# rightboard.net
KiCad netlist of a schematic drawn in EAGLE
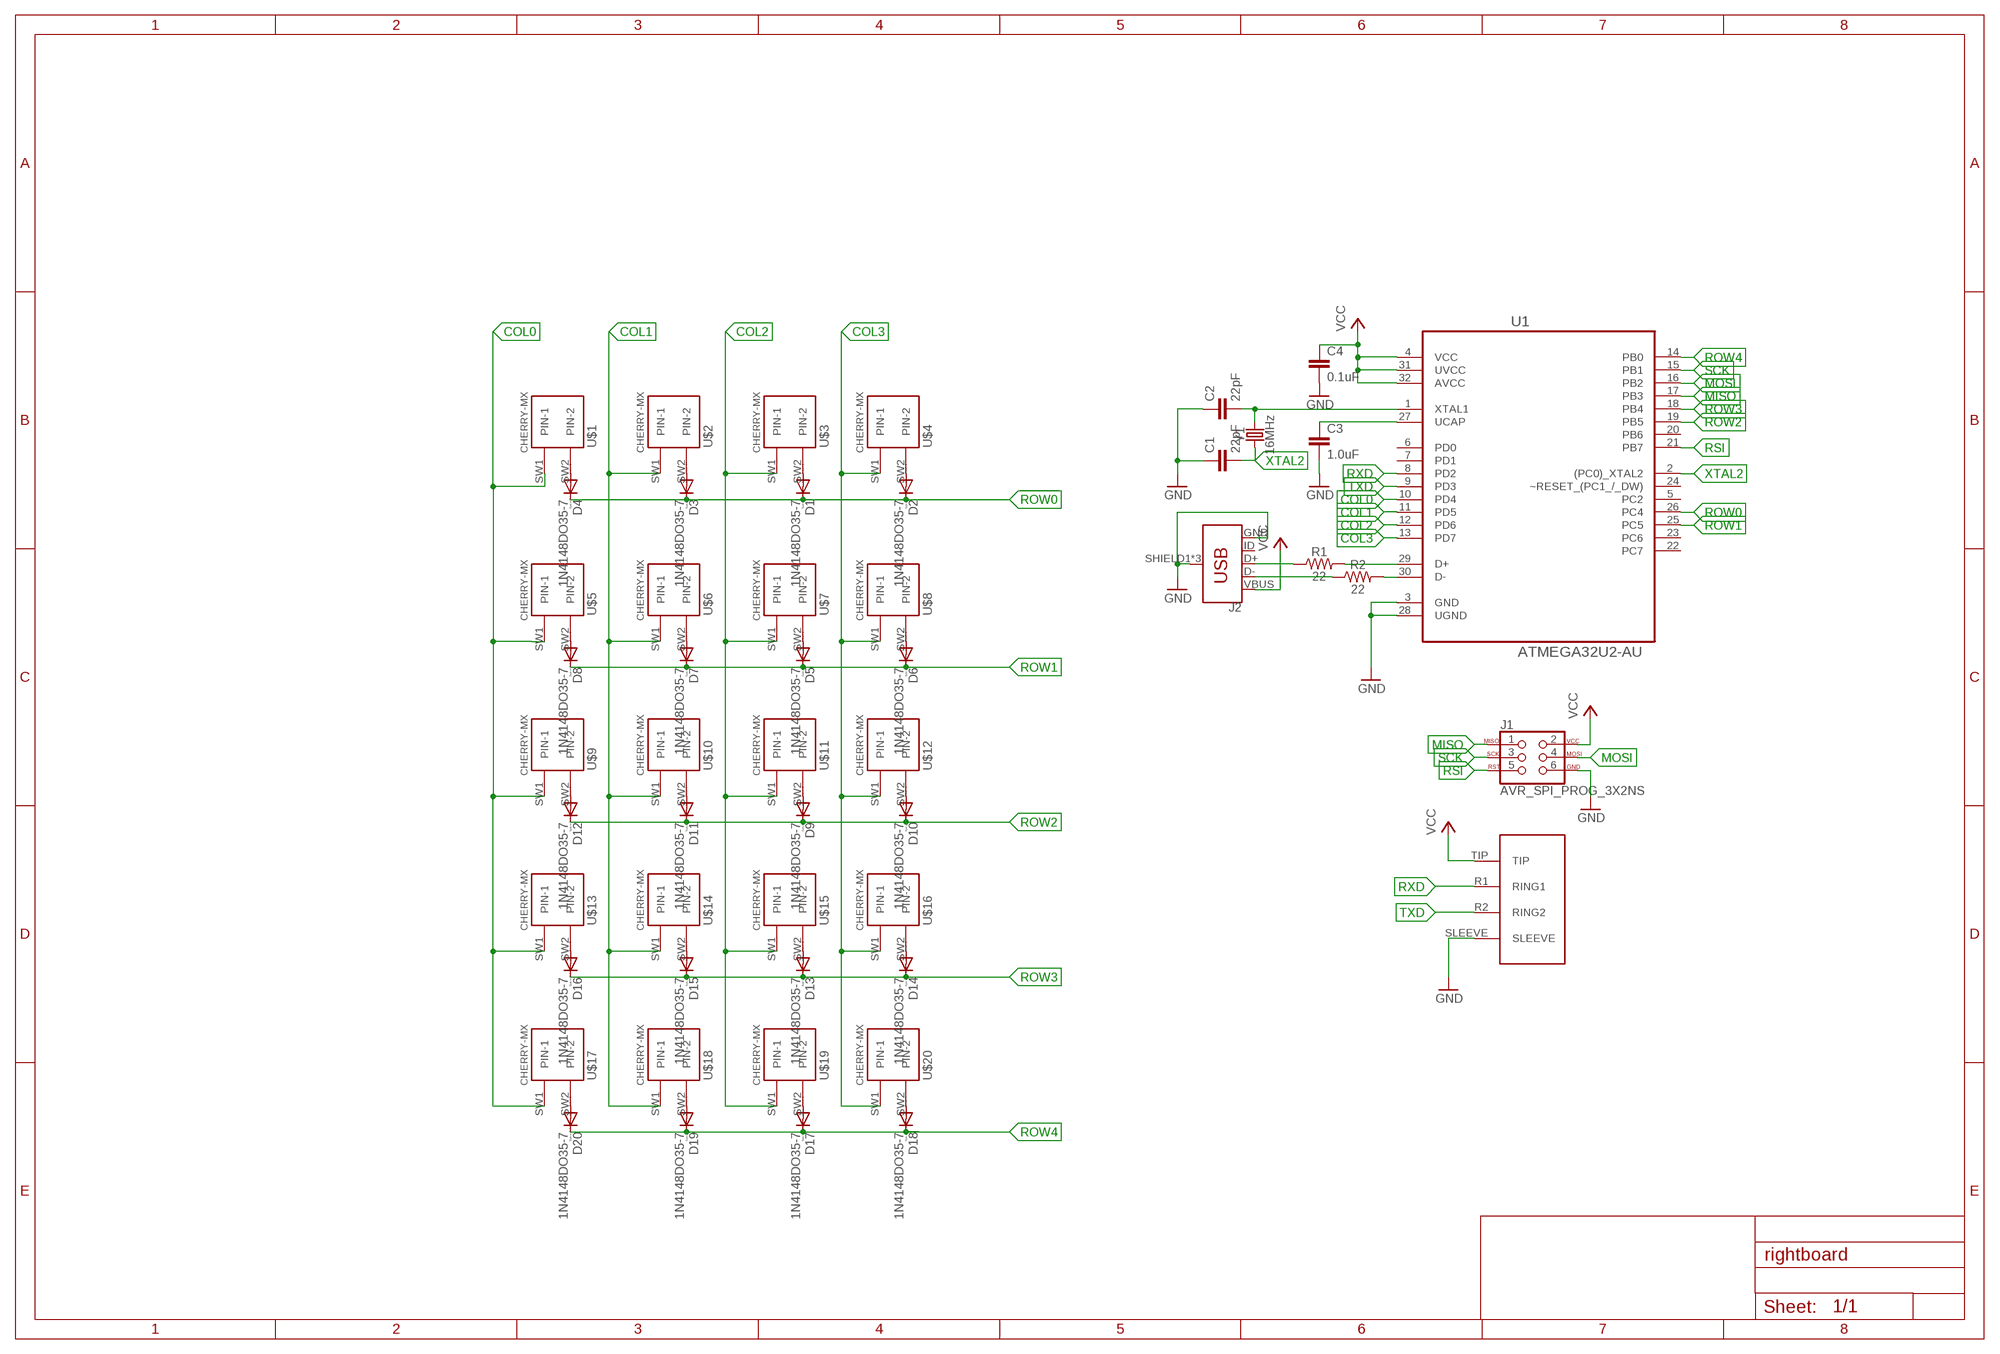
[diagram p0: schematic, sheet 1]

(export (version "E")
  (design (tool "Eeschema 10.0.6"))
  (components
    (comp (ref "C1")
      (value "22pF")
      (footprint "eagle-import:0603")
      (libsource (lib "eagle-import") (part "22PF-0603-50V-5%"))
    )
    (comp (ref "C2")
      (value "22pF")
      (footprint "eagle-import:0603")
      (libsource (lib "eagle-import") (part "22PF-0603-50V-5%"))
    )
    (comp (ref "C3")
      (value "1.0uF")
      (footprint "eagle-import:0603")
      (libsource (lib "eagle-import") (part "1.0UF-0603-16V-10%"))
    )
    (comp (ref "C4")
      (value "0.1uF")
      (footprint "eagle-import:0603")
      (libsource (lib "eagle-import") (part "0.1UF-0603-25V-(+80/-20%)"))
    )
    (comp (ref "D1")
      (value "1N4148DO35-7")
      (footprint "eagle-import:DO35-7")
      (libsource (lib "eagle-import") (part "1N4148DO35-7"))
    )
    (comp (ref "D2")
      (value "1N4148DO35-7")
      (footprint "eagle-import:DO35-7")
      (libsource (lib "eagle-import") (part "1N4148DO35-7"))
    )
    (comp (ref "D3")
      (value "1N4148DO35-7")
      (footprint "eagle-import:DO35-7")
      (libsource (lib "eagle-import") (part "1N4148DO35-7"))
    )
    (comp (ref "D4")
      (value "1N4148DO35-7")
      (footprint "eagle-import:DO35-7")
      (libsource (lib "eagle-import") (part "1N4148DO35-7"))
    )
    (comp (ref "D5")
      (value "1N4148DO35-7")
      (footprint "eagle-import:DO35-7")
      (libsource (lib "eagle-import") (part "1N4148DO35-7"))
    )
    (comp (ref "D6")
      (value "1N4148DO35-7")
      (footprint "eagle-import:DO35-7")
      (libsource (lib "eagle-import") (part "1N4148DO35-7"))
    )
    (comp (ref "D7")
      (value "1N4148DO35-7")
      (footprint "eagle-import:DO35-7")
      (libsource (lib "eagle-import") (part "1N4148DO35-7"))
    )
    (comp (ref "D8")
      (value "1N4148DO35-7")
      (footprint "eagle-import:DO35-7")
      (libsource (lib "eagle-import") (part "1N4148DO35-7"))
    )
    (comp (ref "D9")
      (value "1N4148DO35-7")
      (footprint "eagle-import:DO35-7")
      (libsource (lib "eagle-import") (part "1N4148DO35-7"))
    )
    (comp (ref "D10")
      (value "1N4148DO35-7")
      (footprint "eagle-import:DO35-7")
      (libsource (lib "eagle-import") (part "1N4148DO35-7"))
    )
    (comp (ref "D11")
      (value "1N4148DO35-7")
      (footprint "eagle-import:DO35-7")
      (libsource (lib "eagle-import") (part "1N4148DO35-7"))
    )
    (comp (ref "D12")
      (value "1N4148DO35-7")
      (footprint "eagle-import:DO35-7")
      (libsource (lib "eagle-import") (part "1N4148DO35-7"))
    )
    (comp (ref "D13")
      (value "1N4148DO35-7")
      (footprint "eagle-import:DO35-7")
      (libsource (lib "eagle-import") (part "1N4148DO35-7"))
    )
    (comp (ref "D14")
      (value "1N4148DO35-7")
      (footprint "eagle-import:DO35-7")
      (libsource (lib "eagle-import") (part "1N4148DO35-7"))
    )
    (comp (ref "D15")
      (value "1N4148DO35-7")
      (footprint "eagle-import:DO35-7")
      (libsource (lib "eagle-import") (part "1N4148DO35-7"))
    )
    (comp (ref "D16")
      (value "1N4148DO35-7")
      (footprint "eagle-import:DO35-7")
      (libsource (lib "eagle-import") (part "1N4148DO35-7"))
    )
    (comp (ref "D17")
      (value "1N4148DO35-7")
      (footprint "eagle-import:DO35-7")
      (libsource (lib "eagle-import") (part "1N4148DO35-7"))
    )
    (comp (ref "D18")
      (value "1N4148DO35-7")
      (footprint "eagle-import:DO35-7")
      (libsource (lib "eagle-import") (part "1N4148DO35-7"))
    )
    (comp (ref "D19")
      (value "1N4148DO35-7")
      (footprint "eagle-import:DO35-7")
      (libsource (lib "eagle-import") (part "1N4148DO35-7"))
    )
    (comp (ref "D20")
      (value "1N4148DO35-7")
      (footprint "eagle-import:DO35-7")
      (libsource (lib "eagle-import") (part "1N4148DO35-7"))
    )
    (comp (ref "J1")
      (value "AVR_SPI_PROG_3X2NS")
      (footprint "eagle-import:2X3-NS")
      (libsource (lib "eagle-import") (part "AVR_SPI_PROG_3X2NS"))
    )
    (comp (ref "J2")
      (value "USB_MICRO-B_FEMALE-SMT")
      (footprint "eagle-import:USB-B-MICRO-SMD")
      (libsource (lib "eagle-import") (part "USB_MICRO-B_FEMALE-SMT"))
    )
    (comp (ref "R1")
      (value "22")
      (footprint "eagle-import:0603")
      (libsource (lib "eagle-import") (part "22OHM-0603-1/10W-1%"))
    )
    (comp (ref "R2")
      (value "22")
      (footprint "eagle-import:0603")
      (libsource (lib "eagle-import") (part "22OHM-0603-1/10W-1%"))
    )
    (comp (ref "U$1")
      (value "CHERRY-MX")
      (footprint "eagle-import:CHERRY-MX")
      (libsource (lib "eagle-import") (part "CHERRY-MX"))
    )
    (comp (ref "U$2")
      (value "CHERRY-MX")
      (footprint "eagle-import:CHERRY-MX")
      (libsource (lib "eagle-import") (part "CHERRY-MX"))
    )
    (comp (ref "U$3")
      (value "CHERRY-MX")
      (footprint "eagle-import:CHERRY-MX")
      (libsource (lib "eagle-import") (part "CHERRY-MX"))
    )
    (comp (ref "U$4")
      (value "CHERRY-MX")
      (footprint "eagle-import:CHERRY-MX")
      (libsource (lib "eagle-import") (part "CHERRY-MX"))
    )
    (comp (ref "U$5")
      (value "CHERRY-MX")
      (footprint "eagle-import:CHERRY-MX")
      (libsource (lib "eagle-import") (part "CHERRY-MX"))
    )
    (comp (ref "U$6")
      (value "CHERRY-MX")
      (footprint "eagle-import:CHERRY-MX")
      (libsource (lib "eagle-import") (part "CHERRY-MX"))
    )
    (comp (ref "U$7")
      (value "CHERRY-MX")
      (footprint "eagle-import:CHERRY-MX")
      (libsource (lib "eagle-import") (part "CHERRY-MX"))
    )
    (comp (ref "U$8")
      (value "CHERRY-MX")
      (footprint "eagle-import:CHERRY-MX")
      (libsource (lib "eagle-import") (part "CHERRY-MX"))
    )
    (comp (ref "U$9")
      (value "CHERRY-MX")
      (footprint "eagle-import:CHERRY-MX")
      (libsource (lib "eagle-import") (part "CHERRY-MX"))
    )
    (comp (ref "U$10")
      (value "CHERRY-MX")
      (footprint "eagle-import:CHERRY-MX")
      (libsource (lib "eagle-import") (part "CHERRY-MX"))
    )
    (comp (ref "U$11")
      (value "CHERRY-MX")
      (footprint "eagle-import:CHERRY-MX")
      (libsource (lib "eagle-import") (part "CHERRY-MX"))
    )
    (comp (ref "U$12")
      (value "CHERRY-MX")
      (footprint "eagle-import:CHERRY-MX")
      (libsource (lib "eagle-import") (part "CHERRY-MX"))
    )
    (comp (ref "U$13")
      (value "CHERRY-MX")
      (footprint "eagle-import:CHERRY-MX")
      (libsource (lib "eagle-import") (part "CHERRY-MX"))
    )
    (comp (ref "U$14")
      (value "CHERRY-MX")
      (footprint "eagle-import:CHERRY-MX")
      (libsource (lib "eagle-import") (part "CHERRY-MX"))
    )
    (comp (ref "U$15")
      (value "CHERRY-MX")
      (footprint "eagle-import:CHERRY-MX")
      (libsource (lib "eagle-import") (part "CHERRY-MX"))
    )
    (comp (ref "U$16")
      (value "CHERRY-MX")
      (footprint "eagle-import:CHERRY-MX")
      (libsource (lib "eagle-import") (part "CHERRY-MX"))
    )
    (comp (ref "U$17")
      (value "CHERRY-MX")
      (footprint "eagle-import:CHERRY-MX")
      (libsource (lib "eagle-import") (part "CHERRY-MX"))
    )
    (comp (ref "U$18")
      (value "CHERRY-MX")
      (footprint "eagle-import:CHERRY-MX")
      (libsource (lib "eagle-import") (part "CHERRY-MX"))
    )
    (comp (ref "U$19")
      (value "CHERRY-MX")
      (footprint "eagle-import:CHERRY-MX")
      (libsource (lib "eagle-import") (part "CHERRY-MX"))
    )
    (comp (ref "U$20")
      (value "CHERRY-MX")
      (footprint "eagle-import:CHERRY-MX")
      (libsource (lib "eagle-import") (part "CHERRY-MX"))
    )
    (comp (ref "U$21")
      (value "54-00035")
      (footprint "eagle-import:54-00035")
      (libsource (lib "eagle-import") (part "54-00035"))
    )
    (comp (ref "U1")
      (value "ATMEGA32U2-AU")
      (footprint "eagle-import:QFP80P900X900X120-32N")
      (libsource (lib "eagle-import") (part "ATMEGA32U2-AU"))
    )
    (comp (ref "Y1")
      (value "16MHz")
      (footprint "eagle-import:HC49US")
      (libsource (lib "eagle-import") (part "CRYSTAL-16MHZPTH-HC49US"))
    )
  )
  (nets
    (net (code "1") (name "COL0") (class "Default")
      (node (ref "U$1") (pin "SW1") (pinfunction "PIN-1_SW1") (pintype "bidirectional"))
      (node (ref "U$13") (pin "SW1") (pinfunction "PIN-1_SW1") (pintype "bidirectional"))
      (node (ref "U$17") (pin "SW1") (pinfunction "PIN-1_SW1") (pintype "bidirectional"))
      (node (ref "U$5") (pin "SW1") (pinfunction "PIN-1_SW1") (pintype "bidirectional"))
      (node (ref "U$9") (pin "SW1") (pinfunction "PIN-1_SW1") (pintype "bidirectional"))
      (node (ref "U1") (pin "10") (pinfunction "PD4_10") (pintype "bidirectional"))
    )
    (net (code "2") (name "COL1") (class "Default")
      (node (ref "U$10") (pin "SW1") (pinfunction "PIN-1_SW1") (pintype "bidirectional"))
      (node (ref "U$14") (pin "SW1") (pinfunction "PIN-1_SW1") (pintype "bidirectional"))
      (node (ref "U$18") (pin "SW1") (pinfunction "PIN-1_SW1") (pintype "bidirectional"))
      (node (ref "U$2") (pin "SW1") (pinfunction "PIN-1_SW1") (pintype "bidirectional"))
      (node (ref "U$6") (pin "SW1") (pinfunction "PIN-1_SW1") (pintype "bidirectional"))
      (node (ref "U1") (pin "11") (pinfunction "PD5_11") (pintype "bidirectional"))
    )
    (net (code "3") (name "COL2") (class "Default")
      (node (ref "U$11") (pin "SW1") (pinfunction "PIN-1_SW1") (pintype "bidirectional"))
      (node (ref "U$15") (pin "SW1") (pinfunction "PIN-1_SW1") (pintype "bidirectional"))
      (node (ref "U$19") (pin "SW1") (pinfunction "PIN-1_SW1") (pintype "bidirectional"))
      (node (ref "U$3") (pin "SW1") (pinfunction "PIN-1_SW1") (pintype "bidirectional"))
      (node (ref "U$7") (pin "SW1") (pinfunction "PIN-1_SW1") (pintype "bidirectional"))
      (node (ref "U1") (pin "12") (pinfunction "PD6_12") (pintype "bidirectional"))
    )
    (net (code "4") (name "COL3") (class "Default")
      (node (ref "U$12") (pin "SW1") (pinfunction "PIN-1_SW1") (pintype "bidirectional"))
      (node (ref "U$16") (pin "SW1") (pinfunction "PIN-1_SW1") (pintype "bidirectional"))
      (node (ref "U$20") (pin "SW1") (pinfunction "PIN-1_SW1") (pintype "bidirectional"))
      (node (ref "U$4") (pin "SW1") (pinfunction "PIN-1_SW1") (pintype "bidirectional"))
      (node (ref "U$8") (pin "SW1") (pinfunction "PIN-1_SW1") (pintype "bidirectional"))
      (node (ref "U1") (pin "13") (pinfunction "PD7_13") (pintype "bidirectional"))
    )
    (net (code "5") (name "GND") (class "Default")
      (node (ref "C1") (pin "1") (pinfunction "1_1") (pintype "passive"))
      (node (ref "C2") (pin "1") (pinfunction "1_1") (pintype "passive"))
      (node (ref "C3") (pin "2") (pinfunction "2_2") (pintype "passive"))
      (node (ref "C4") (pin "2") (pinfunction "2_2") (pintype "passive"))
      (node (ref "J1") (pin "6") (pinfunction "6_6") (pintype "passive"))
      (node (ref "J2") (pin "GND") (pinfunction "GND_GND") (pintype "power_in"))
      (node (ref "J2") (pin "SHIELD1") (pinfunction "SHIELD_SHIELD1") (pintype "bidirectional"))
      (node (ref "J2") (pin "SHIELD2") (pinfunction "SHIELD_SHIELD2") (pintype "bidirectional"))
      (node (ref "J2") (pin "SHIELD3") (pinfunction "SHIELD_SHIELD3") (pintype "bidirectional"))
      (node (ref "U$21") (pin "SLEEVE") (pinfunction "SLEEVE_SLEEVE") (pintype "bidirectional"))
      (node (ref "U1") (pin "28") (pinfunction "UGND_28") (pintype "passive"))
      (node (ref "U1") (pin "3") (pinfunction "GND_3") (pintype "passive"))
    )
    (net (code "6") (name "MISO") (class "Default")
      (node (ref "J1") (pin "1") (pinfunction "1_1") (pintype "passive"))
      (node (ref "U1") (pin "17") (pinfunction "PB3_17") (pintype "bidirectional"))
    )
    (net (code "7") (name "MOSI") (class "Default")
      (node (ref "J1") (pin "4") (pinfunction "4_4") (pintype "passive"))
      (node (ref "U1") (pin "16") (pinfunction "PB2_16") (pintype "bidirectional"))
    )
    (net (code "8") (name "Net-(J2-PadD+)") (class "Default")
      (node (ref "J2") (pin "D+") (pinfunction "D+_D+") (pintype "bidirectional"))
      (node (ref "R1") (pin "1") (pinfunction "1_1") (pintype "passive"))
    )
    (net (code "9") (name "Net-(J2-PadD-)") (class "Default")
      (node (ref "J2") (pin "D-") (pinfunction "D-_D-") (pintype "bidirectional"))
      (node (ref "R2") (pin "1") (pinfunction "1_1") (pintype "passive"))
    )
    (net (code "10") (name "Net-(U$1-PIN-2)") (class "Default")
      (node (ref "D4") (pin "A") (pinfunction "A_A") (pintype "passive"))
      (node (ref "U$1") (pin "SW2") (pinfunction "PIN-2_SW2") (pintype "bidirectional"))
    )
    (net (code "11") (name "Net-(U$2-PIN-2)") (class "Default")
      (node (ref "D3") (pin "A") (pinfunction "A_A") (pintype "passive"))
      (node (ref "U$2") (pin "SW2") (pinfunction "PIN-2_SW2") (pintype "bidirectional"))
    )
    (net (code "12") (name "Net-(U$3-PIN-2)") (class "Default")
      (node (ref "D1") (pin "A") (pinfunction "A_A") (pintype "passive"))
      (node (ref "U$3") (pin "SW2") (pinfunction "PIN-2_SW2") (pintype "bidirectional"))
    )
    (net (code "13") (name "Net-(U$4-PIN-2)") (class "Default")
      (node (ref "D2") (pin "A") (pinfunction "A_A") (pintype "passive"))
      (node (ref "U$4") (pin "SW2") (pinfunction "PIN-2_SW2") (pintype "bidirectional"))
    )
    (net (code "14") (name "Net-(U$5-PIN-2)") (class "Default")
      (node (ref "D8") (pin "A") (pinfunction "A_A") (pintype "passive"))
      (node (ref "U$5") (pin "SW2") (pinfunction "PIN-2_SW2") (pintype "bidirectional"))
    )
    (net (code "15") (name "Net-(U$6-PIN-2)") (class "Default")
      (node (ref "D7") (pin "A") (pinfunction "A_A") (pintype "passive"))
      (node (ref "U$6") (pin "SW2") (pinfunction "PIN-2_SW2") (pintype "bidirectional"))
    )
    (net (code "16") (name "Net-(U$7-PIN-2)") (class "Default")
      (node (ref "D5") (pin "A") (pinfunction "A_A") (pintype "passive"))
      (node (ref "U$7") (pin "SW2") (pinfunction "PIN-2_SW2") (pintype "bidirectional"))
    )
    (net (code "17") (name "Net-(U$8-PIN-2)") (class "Default")
      (node (ref "D6") (pin "A") (pinfunction "A_A") (pintype "passive"))
      (node (ref "U$8") (pin "SW2") (pinfunction "PIN-2_SW2") (pintype "bidirectional"))
    )
    (net (code "18") (name "Net-(U$9-PIN-2)") (class "Default")
      (node (ref "D12") (pin "A") (pinfunction "A_A") (pintype "passive"))
      (node (ref "U$9") (pin "SW2") (pinfunction "PIN-2_SW2") (pintype "bidirectional"))
    )
    (net (code "19") (name "Net-(U$10-PIN-2)") (class "Default")
      (node (ref "D11") (pin "A") (pinfunction "A_A") (pintype "passive"))
      (node (ref "U$10") (pin "SW2") (pinfunction "PIN-2_SW2") (pintype "bidirectional"))
    )
    (net (code "20") (name "Net-(U$11-PIN-2)") (class "Default")
      (node (ref "D9") (pin "A") (pinfunction "A_A") (pintype "passive"))
      (node (ref "U$11") (pin "SW2") (pinfunction "PIN-2_SW2") (pintype "bidirectional"))
    )
    (net (code "21") (name "Net-(U$12-PIN-2)") (class "Default")
      (node (ref "D10") (pin "A") (pinfunction "A_A") (pintype "passive"))
      (node (ref "U$12") (pin "SW2") (pinfunction "PIN-2_SW2") (pintype "bidirectional"))
    )
    (net (code "22") (name "Net-(U$13-PIN-2)") (class "Default")
      (node (ref "D16") (pin "A") (pinfunction "A_A") (pintype "passive"))
      (node (ref "U$13") (pin "SW2") (pinfunction "PIN-2_SW2") (pintype "bidirectional"))
    )
    (net (code "23") (name "Net-(U$14-PIN-2)") (class "Default")
      (node (ref "D15") (pin "A") (pinfunction "A_A") (pintype "passive"))
      (node (ref "U$14") (pin "SW2") (pinfunction "PIN-2_SW2") (pintype "bidirectional"))
    )
    (net (code "24") (name "Net-(U$15-PIN-2)") (class "Default")
      (node (ref "D13") (pin "A") (pinfunction "A_A") (pintype "passive"))
      (node (ref "U$15") (pin "SW2") (pinfunction "PIN-2_SW2") (pintype "bidirectional"))
    )
    (net (code "25") (name "Net-(U$16-PIN-2)") (class "Default")
      (node (ref "D14") (pin "A") (pinfunction "A_A") (pintype "passive"))
      (node (ref "U$16") (pin "SW2") (pinfunction "PIN-2_SW2") (pintype "bidirectional"))
    )
    (net (code "26") (name "Net-(U$17-PIN-2)") (class "Default")
      (node (ref "D20") (pin "A") (pinfunction "A_A") (pintype "passive"))
      (node (ref "U$17") (pin "SW2") (pinfunction "PIN-2_SW2") (pintype "bidirectional"))
    )
    (net (code "27") (name "Net-(U$18-PIN-2)") (class "Default")
      (node (ref "D19") (pin "A") (pinfunction "A_A") (pintype "passive"))
      (node (ref "U$18") (pin "SW2") (pinfunction "PIN-2_SW2") (pintype "bidirectional"))
    )
    (net (code "28") (name "Net-(U$19-PIN-2)") (class "Default")
      (node (ref "D17") (pin "A") (pinfunction "A_A") (pintype "passive"))
      (node (ref "U$19") (pin "SW2") (pinfunction "PIN-2_SW2") (pintype "bidirectional"))
    )
    (net (code "29") (name "Net-(U$20-PIN-2)") (class "Default")
      (node (ref "D18") (pin "A") (pinfunction "A_A") (pintype "passive"))
      (node (ref "U$20") (pin "SW2") (pinfunction "PIN-2_SW2") (pintype "bidirectional"))
    )
    (net (code "30") (name "Net-(U1-D+)") (class "Default")
      (node (ref "R1") (pin "2") (pinfunction "2_2") (pintype "passive"))
      (node (ref "U1") (pin "29") (pinfunction "D+_29") (pintype "bidirectional"))
    )
    (net (code "31") (name "Net-(U1-D-)") (class "Default")
      (node (ref "R2") (pin "2") (pinfunction "2_2") (pintype "passive"))
      (node (ref "U1") (pin "30") (pinfunction "D-_30") (pintype "bidirectional"))
    )
    (net (code "32") (name "Net-(U1-UCAP)") (class "Default")
      (node (ref "C3") (pin "1") (pinfunction "1_1") (pintype "passive"))
      (node (ref "U1") (pin "27") (pinfunction "UCAP_27") (pintype "power_in"))
    )
    (net (code "33") (name "Net-(U1-XTAL1)") (class "Default")
      (node (ref "C2") (pin "2") (pinfunction "2_2") (pintype "passive"))
      (node (ref "U1") (pin "1") (pinfunction "XTAL1_1") (pintype "input"))
      (node (ref "Y1") (pin "2") (pinfunction "2_2") (pintype "passive"))
    )
    (net (code "34") (name "ROW0") (class "Default")
      (node (ref "D1") (pin "C") (pinfunction "C_C") (pintype "passive"))
      (node (ref "D2") (pin "C") (pinfunction "C_C") (pintype "passive"))
      (node (ref "D3") (pin "C") (pinfunction "C_C") (pintype "passive"))
      (node (ref "D4") (pin "C") (pinfunction "C_C") (pintype "passive"))
      (node (ref "U1") (pin "26") (pinfunction "PC4_26") (pintype "bidirectional"))
    )
    (net (code "35") (name "ROW1") (class "Default")
      (node (ref "D5") (pin "C") (pinfunction "C_C") (pintype "passive"))
      (node (ref "D6") (pin "C") (pinfunction "C_C") (pintype "passive"))
      (node (ref "D7") (pin "C") (pinfunction "C_C") (pintype "passive"))
      (node (ref "D8") (pin "C") (pinfunction "C_C") (pintype "passive"))
      (node (ref "U1") (pin "25") (pinfunction "PC5_25") (pintype "bidirectional"))
    )
    (net (code "36") (name "ROW2") (class "Default")
      (node (ref "D10") (pin "C") (pinfunction "C_C") (pintype "passive"))
      (node (ref "D11") (pin "C") (pinfunction "C_C") (pintype "passive"))
      (node (ref "D12") (pin "C") (pinfunction "C_C") (pintype "passive"))
      (node (ref "D9") (pin "C") (pinfunction "C_C") (pintype "passive"))
      (node (ref "U1") (pin "19") (pinfunction "PB5_19") (pintype "bidirectional"))
    )
    (net (code "37") (name "ROW3") (class "Default")
      (node (ref "D13") (pin "C") (pinfunction "C_C") (pintype "passive"))
      (node (ref "D14") (pin "C") (pinfunction "C_C") (pintype "passive"))
      (node (ref "D15") (pin "C") (pinfunction "C_C") (pintype "passive"))
      (node (ref "D16") (pin "C") (pinfunction "C_C") (pintype "passive"))
      (node (ref "U1") (pin "18") (pinfunction "PB4_18") (pintype "bidirectional"))
    )
    (net (code "38") (name "ROW4") (class "Default")
      (node (ref "D17") (pin "C") (pinfunction "C_C") (pintype "passive"))
      (node (ref "D18") (pin "C") (pinfunction "C_C") (pintype "passive"))
      (node (ref "D19") (pin "C") (pinfunction "C_C") (pintype "passive"))
      (node (ref "D20") (pin "C") (pinfunction "C_C") (pintype "passive"))
      (node (ref "U1") (pin "14") (pinfunction "PB0_14") (pintype "bidirectional"))
    )
    (net (code "39") (name "RSI") (class "Default")
      (node (ref "J1") (pin "5") (pinfunction "5_5") (pintype "passive"))
      (node (ref "U1") (pin "21") (pinfunction "PB7_21") (pintype "bidirectional"))
    )
    (net (code "40") (name "RXD") (class "Default")
      (node (ref "U$21") (pin "R1") (pinfunction "RING1_R1") (pintype "bidirectional"))
      (node (ref "U1") (pin "8") (pinfunction "PD2_8") (pintype "bidirectional"))
    )
    (net (code "41") (name "SCK") (class "Default")
      (node (ref "J1") (pin "3") (pinfunction "3_3") (pintype "passive"))
      (node (ref "U1") (pin "15") (pinfunction "PB1_15") (pintype "bidirectional"))
    )
    (net (code "42") (name "TXD") (class "Default")
      (node (ref "U$21") (pin "R2") (pinfunction "RING2_R2") (pintype "bidirectional"))
      (node (ref "U1") (pin "9") (pinfunction "PD3_9") (pintype "bidirectional"))
    )
    (net (code "43") (name "VCC") (class "Default")
      (node (ref "C4") (pin "1") (pinfunction "1_1") (pintype "passive"))
      (node (ref "J1") (pin "2") (pinfunction "2_2") (pintype "passive"))
      (node (ref "J2") (pin "VBUS") (pinfunction "VBUS_VBUS") (pintype "power_in"))
      (node (ref "U$21") (pin "TIP") (pinfunction "TIP_TIP") (pintype "bidirectional"))
      (node (ref "U1") (pin "31") (pinfunction "UVCC_31") (pintype "power_in"))
      (node (ref "U1") (pin "32") (pinfunction "AVCC_32") (pintype "power_in"))
      (node (ref "U1") (pin "4") (pinfunction "VCC_4") (pintype "power_in"))
    )
    (net (code "44") (name "XTAL2") (class "Default")
      (node (ref "C1") (pin "2") (pinfunction "2_2") (pintype "passive"))
      (node (ref "U1") (pin "2") (pinfunction "(PC0)_XTAL2_2") (pintype "bidirectional"))
      (node (ref "Y1") (pin "1") (pinfunction "1_1") (pintype "passive"))
    )
    (net (code "45") (name "unconnected-(J2-PadID)") (class "Default")
      (node (ref "J2") (pin "ID") (pinfunction "ID_ID") (pintype "bidirectional"))
    )
    (net (code "46") (name "unconnected-(U1-PB6-Pad20)") (class "Default")
      (node (ref "U1") (pin "20") (pinfunction "PB6_20") (pintype "bidirectional"))
    )
    (net (code "47") (name "unconnected-(U1-PC2-Pad5)") (class "Default")
      (node (ref "U1") (pin "5") (pinfunction "PC2_5") (pintype "bidirectional"))
    )
    (net (code "48") (name "unconnected-(U1-PC6-Pad23)") (class "Default")
      (node (ref "U1") (pin "23") (pinfunction "PC6_23") (pintype "bidirectional"))
    )
    (net (code "49") (name "unconnected-(U1-PC7-Pad22)") (class "Default")
      (node (ref "U1") (pin "22") (pinfunction "PC7_22") (pintype "bidirectional"))
    )
    (net (code "50") (name "unconnected-(U1-PD0-Pad6)") (class "Default")
      (node (ref "U1") (pin "6") (pinfunction "PD0_6") (pintype "bidirectional"))
    )
    (net (code "51") (name "unconnected-(U1-PD1-Pad7)") (class "Default")
      (node (ref "U1") (pin "7") (pinfunction "PD1_7") (pintype "bidirectional"))
    )
    (net (code "52") (name "unconnected-(U1-~{RESET_(PC1_{slash}_DW})-Pad24)") (class "Default")
      (node (ref "U1") (pin "24") (pinfunction "~{RESET_(PC1_/_DW})_24") (pintype "bidirectional"))
    )
  )
)
